# sch_camera.net
KiCad netlist of a schematic drawn in Altium Designer
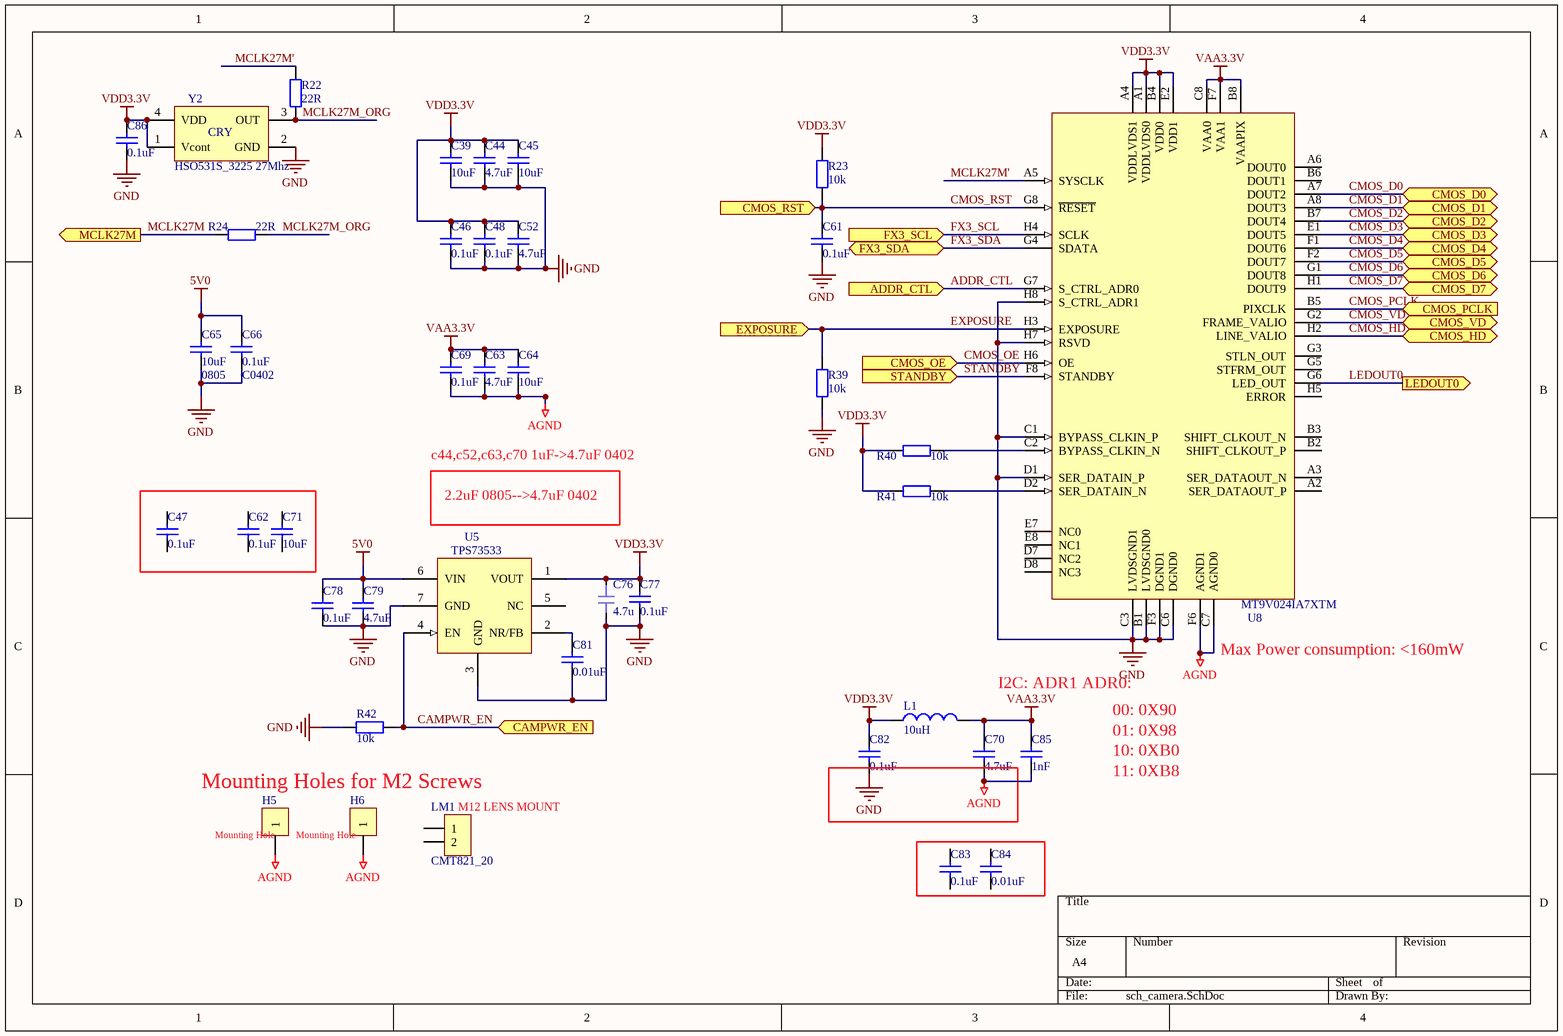
[diagram p0: sch_camera.SchDoc]

(export (version "E")
  (design (tool "Eeschema 10.0.6"))
  (components
    (comp (ref "C39")
      (value "10uF")
      (footprint "0805C")
      (description "Capacitor")
      (fields (field (name "PUBLISHER") "Altium Limited"))
      (libsource (lib "Miscellaneous Devices") (part "Cap"))
    )
    (comp (ref "C44")
      (value "4.7uF")
      (footprint "0402C")
      (description "Capacitor")
      (fields (field (name "PUBLISHER") "Altium Limited"))
      (libsource (lib "Miscellaneous Devices") (part "Cap"))
    )
    (comp (ref "C45")
      (value "10uF")
      (footprint "0805C")
      (description "Capacitor")
      (fields (field (name "PUBLISHER") "Altium Limited"))
      (libsource (lib "Miscellaneous Devices") (part "Cap"))
    )
    (comp (ref "C46")
      (value "0.1uF")
      (footprint "0402C")
      (description "Capacitor")
      (fields (field (name "PUBLISHER") "Altium Limited"))
      (libsource (lib "Miscellaneous Devices") (part "Cap"))
    )
    (comp (ref "C47")
      (value "0.1uF")
      (footprint "0402C")
      (description "Capacitor")
      (fields (field (name "PUBLISHER") "Altium Limited"))
      (libsource (lib "Miscellaneous Devices") (part "Cap"))
    )
    (comp (ref "C48")
      (value "0.1uF")
      (footprint "0402C")
      (description "Capacitor")
      (fields (field (name "PUBLISHER") "Altium Limited"))
      (libsource (lib "Miscellaneous Devices") (part "Cap"))
    )
    (comp (ref "C52")
      (value "4.7uF")
      (footprint "0402C")
      (description "Capacitor")
      (fields (field (name "PUBLISHER") "Altium Limited"))
      (libsource (lib "Miscellaneous Devices") (part "Cap"))
    )
    (comp (ref "C61")
      (value "0.1uF")
      (footprint "0402C_L")
      (description "Capacitor")
      (fields (field (name "PUBLISHER") "Altium Limited"))
      (libsource (lib "Miscellaneous Devices") (part "Cap"))
    )
    (comp (ref "C62")
      (value "0.1uF")
      (footprint "0402C")
      (description "Capacitor")
      (fields (field (name "PUBLISHER") "Altium Limited"))
      (libsource (lib "Miscellaneous Devices") (part "Cap"))
    )
    (comp (ref "C63")
      (value "4.7uF")
      (footprint "0402C")
      (description "Capacitor")
      (fields (field (name "PUBLISHER") "Altium Limited"))
      (libsource (lib "Miscellaneous Devices") (part "Cap"))
    )
    (comp (ref "C64")
      (value "10uF")
      (footprint "0805C")
      (description "Capacitor")
      (fields (field (name "PUBLISHER") "Altium Limited"))
      (libsource (lib "Miscellaneous Devices") (part "Cap"))
    )
    (comp (ref "C65")
      (value "10uF")
      (footprint "0805C")
      (description "Capacitor")
      (fields (field (name "ALTIUM_VALUE") "0805") (field (name "PUBLISHER") "Altium Limited"))
      (libsource (lib "Miscellaneous Devices") (part "Cap"))
    )
    (comp (ref "C66")
      (value "0.1uF")
      (footprint "0402C")
      (description "Capacitor")
      (fields (field (name "ALTIUM_VALUE") "C0402") (field (name "PUBLISHER") "Altium Limited"))
      (libsource (lib "Miscellaneous Devices") (part "Cap"))
    )
    (comp (ref "C69")
      (value "0.1uF")
      (footprint "0402C")
      (description "Capacitor")
      (fields (field (name "PUBLISHER") "Altium Limited"))
      (libsource (lib "Miscellaneous Devices") (part "Cap"))
    )
    (comp (ref "C70")
      (value "4.7uF")
      (footprint "0402C")
      (description "Capacitor")
      (fields (field (name "PUBLISHER") "Altium Limited"))
      (libsource (lib "Miscellaneous Devices") (part "Cap"))
    )
    (comp (ref "C71")
      (value "10uF")
      (footprint "0805C")
      (description "Capacitor")
      (fields (field (name "PUBLISHER") "Altium Limited"))
      (libsource (lib "Miscellaneous Devices") (part "Cap"))
    )
    (comp (ref "C76")
      (value "4.7u")
      (footprint "0402C_L")
      (description "CC0402MRX5R5BB475")
      (libsource (lib "V0P1") (part "cap0402"))
    )
    (comp (ref "C77")
      (value "0.1uF")
      (footprint "0402C_L")
      (description "Capacitor")
      (fields (field (name "PUBLISHER") "Altium Limited"))
      (libsource (lib "Miscellaneous Devices") (part "Cap"))
    )
    (comp (ref "C78")
      (value "0.1uF")
      (footprint "0402C")
      (description "Capacitor")
      (fields (field (name "PUBLISHER") "Altium Limited"))
      (libsource (lib "Miscellaneous Devices") (part "Cap"))
    )
    (comp (ref "C79")
      (value "4.7uF")
      (footprint "0402C_L")
      (description "Capacitor")
      (fields (field (name "Comment") "1uF") (field (name "PUBLISHER") "Altium Limited"))
      (libsource (lib "Miscellaneous Devices") (part "Cap"))
    )
    (comp (ref "C81")
      (value "0.01uF")
      (footprint "0402C_L")
      (description "Capacitor")
      (fields (field (name "PUBLISHER") "Altium Limited"))
      (libsource (lib "Miscellaneous Devices") (part "Cap"))
    )
    (comp (ref "C82")
      (value "0.1uF")
      (footprint "0402C_L")
      (description "Capacitor")
      (fields (field (name "PUBLISHER") "Altium Limited"))
      (libsource (lib "Miscellaneous Devices") (part "Cap"))
    )
    (comp (ref "C83")
      (value "0.1uF")
      (footprint "0402C_L")
      (description "Capacitor")
      (fields (field (name "PUBLISHER") "Altium Limited"))
      (libsource (lib "Miscellaneous Devices") (part "Cap"))
    )
    (comp (ref "C84")
      (value "0.01uF")
      (footprint "0402C_L")
      (description "Capacitor")
      (fields (field (name "PUBLISHER") "Altium Limited"))
      (libsource (lib "Miscellaneous Devices") (part "Cap"))
    )
    (comp (ref "C85")
      (value "1nF")
      (footprint "0402C_L")
      (description "Capacitor")
      (fields (field (name "PUBLISHER") "Altium Limited"))
      (libsource (lib "Miscellaneous Devices") (part "Cap"))
    )
    (comp (ref "C86")
      (value "0.1uF")
      (footprint "0402C_L")
      (description "Capacitor")
      (fields (field (name "PUBLISHER") "Altium Limited"))
      (libsource (lib "Miscellaneous Devices") (part "Cap"))
    )
    (comp (ref "H5")
      (value "CON1")
      (footprint "PAD_M3_D350_450")
      (description "Connector")
      (libsource (lib "SuperSchLib") (part "CON1"))
    )
    (comp (ref "H6")
      (value "CON1")
      (footprint "PAD_M3_D350_450")
      (description "Connector")
      (libsource (lib "SuperSchLib") (part "CON1"))
    )
    (comp (ref "L1")
      (value "10uH")
      (footprint "0805R")
      (description "Inductor")
      (libsource (lib "SWUST_ROBOT") (part "Inductor"))
    )
    (comp (ref "LM1")
      (value "CMT821_20")
      (footprint "PAD_M3_D350_450")
      (description "Connector")
      (libsource (lib "SuperSchLib") (part "CON2"))
    )
    (comp (ref "R22")
      (value "22R")
      (footprint "0402R_L")
      (description "Resistor")
      (fields (field (name "Comment") "0R") (field (name "PUBLISHER") "Altium Limited"))
      (libsource (lib "SZG") (part "Resistor"))
    )
    (comp (ref "R23")
      (value "10k")
      (footprint "0402R_L")
      (description "Resistor")
      (fields (field (name "Comment") "10K") (field (name "PUBLISHER") "Altium Limited"))
      (libsource (lib "") (part "Resistor_2"))
    )
    (comp (ref "R24")
      (value "22R")
      (footprint "0402R")
      (description "Resistor")
      (fields (field (name "PUBLISHER") "Altium Limited"))
      (libsource (lib "") (part "Resistor_1"))
    )
    (comp (ref "R39")
      (value "10k")
      (footprint "0402R_L")
      (description "Resistor")
      (fields (field (name "Comment") "10K") (field (name "PUBLISHER") "Altium Limited"))
      (libsource (lib "SZG") (part "Resistor"))
    )
    (comp (ref "R40")
      (value "10k")
      (footprint "0402R_L")
      (description "Resistor")
      (fields (field (name "Comment") "10K") (field (name "PUBLISHER") "Altium Limited"))
      (libsource (lib "") (part "Resistor_3"))
    )
    (comp (ref "R41")
      (value "10k")
      (footprint "0402R_L")
      (description "Resistor")
      (fields (field (name "Comment") "10K") (field (name "PUBLISHER") "Altium Limited"))
      (libsource (lib "") (part "Resistor_3"))
    )
    (comp (ref "R42")
      (value "10k")
      (footprint "0402R_L")
      (description "Resistor")
      (fields (field (name "Comment") "10K") (field (name "PUBLISHER") "Altium Limited"))
      (libsource (lib "") (part "Resistor_3"))
    )
    (comp (ref "U5")
      (value "TPS73533")
      (footprint "SON6_P65L21W21H8_DRV")
      (libsource (lib "SZG") (part "TPS73533"))
    )
    (comp (ref "U8")
      (value "MT9V024IA7XTM")
      (footprint "IBGA52_8X8_P100L90W90H90R")
      (libsource (lib "SZG") (part "MT9V024IA7XTM"))
    )
    (comp (ref "Y2")
      (value "HSO531S_3225 27Mhz")
      (footprint "XTAL_3225")
      (description "有源晶振")
      (libsource (lib "超集元件库") (part "CRY"))
    )
  )
  (nets
    (net (code "1") (name "/ADDR_CTL") (class "Default")
      (node (ref "U8") (pin "G7") (pinfunction "S_CTRL_ADR0_G7") (pintype "input"))
    )
    (net (code "2") (name "/CAMPWR_EN") (class "Default")
      (node (ref "R42") (pin "1") (pinfunction "1_1") (pintype "passive"))
      (node (ref "U5") (pin "4") (pinfunction "EN_4") (pintype "input"))
    )
    (net (code "3") (name "/CMOS_D0") (class "Default")
      (node (ref "U8") (pin "A7") (pinfunction "DOUT2_A7") (pintype "passive"))
    )
    (net (code "4") (name "/CMOS_D1") (class "Default")
      (node (ref "U8") (pin "A8") (pinfunction "DOUT3_A8") (pintype "passive"))
    )
    (net (code "5") (name "/CMOS_D2") (class "Default")
      (node (ref "U8") (pin "B7") (pinfunction "DOUT4_B7") (pintype "passive"))
    )
    (net (code "6") (name "/CMOS_D3") (class "Default")
      (node (ref "U8") (pin "E1") (pinfunction "DOUT5_E1") (pintype "passive"))
    )
    (net (code "7") (name "/CMOS_D4") (class "Default")
      (node (ref "U8") (pin "F1") (pinfunction "DOUT6_F1") (pintype "passive"))
    )
    (net (code "8") (name "/CMOS_D5") (class "Default")
      (node (ref "U8") (pin "F2") (pinfunction "DOUT7_F2") (pintype "passive"))
    )
    (net (code "9") (name "/CMOS_D6") (class "Default")
      (node (ref "U8") (pin "G1") (pinfunction "DOUT8_G1") (pintype "passive"))
    )
    (net (code "10") (name "/CMOS_D7") (class "Default")
      (node (ref "U8") (pin "H1") (pinfunction "DOUT9_H1") (pintype "passive"))
    )
    (net (code "11") (name "/CMOS_HD") (class "Default")
      (node (ref "U8") (pin "H2") (pinfunction "LINE_VALIO_H2") (pintype "passive"))
    )
    (net (code "12") (name "/CMOS_OE") (class "Default")
      (node (ref "U8") (pin "H6") (pinfunction "OE_H6") (pintype "input"))
    )
    (net (code "13") (name "/CMOS_PCLK") (class "Default")
      (node (ref "U8") (pin "B5") (pinfunction "PIXCLK_B5") (pintype "passive"))
    )
    (net (code "14") (name "/CMOS_RST") (class "Default")
      (node (ref "C61") (pin "2") (pinfunction "2_2") (pintype "passive"))
      (node (ref "R23") (pin "1") (pinfunction "1_1") (pintype "passive"))
      (node (ref "U8") (pin "G8") (pinfunction "~{RESET}_G8") (pintype "input"))
    )
    (net (code "15") (name "/CMOS_VD") (class "Default")
      (node (ref "U8") (pin "G2") (pinfunction "FRAME_VALIO_G2") (pintype "passive"))
    )
    (net (code "16") (name "/EXPOSURE") (class "Default")
      (node (ref "R39") (pin "1") (pinfunction "1_1") (pintype "passive"))
      (node (ref "U8") (pin "H3") (pinfunction "EXPOSURE_H3") (pintype "input"))
    )
    (net (code "17") (name "/FX3_SCL") (class "Default")
      (node (ref "U8") (pin "H4") (pinfunction "SCLK_H4") (pintype "input"))
    )
    (net (code "18") (name "/FX3_SDA") (class "Default")
      (node (ref "U8") (pin "G4") (pinfunction "SDATA_G4") (pintype "passive"))
    )
    (net (code "19") (name "/LEDOUT0") (class "Default")
      (node (ref "U8") (pin "G6") (pinfunction "LED_OUT_G6") (pintype "passive"))
    )
    (net (code "20") (name "/MCLK27M") (class "Default")
      (node (ref "R24") (pin "1") (pinfunction "1_1") (pintype "passive"))
    )
    (net (code "21") (name "/MCLK27M'") (class "Default")
      (node (ref "R22") (pin "1") (pinfunction "1_1") (pintype "passive"))
      (node (ref "U8") (pin "A5") (pinfunction "SYSCLK_A5") (pintype "input"))
    )
    (net (code "22") (name "/MCLK27M_ORG") (class "Default")
      (node (ref "R22") (pin "2") (pinfunction "2_2") (pintype "passive"))
      (node (ref "R24") (pin "2") (pinfunction "2_2") (pintype "passive"))
      (node (ref "Y2") (pin "3") (pinfunction "OUT_3") (pintype "passive"))
    )
    (net (code "23") (name "/STANDBY") (class "Default")
      (node (ref "U8") (pin "F8") (pinfunction "STANDBY_F8") (pintype "input"))
    )
    (net (code "24") (name "5V0") (class "Default")
      (node (ref "C65") (pin "2") (pinfunction "2_2") (pintype "passive"))
      (node (ref "C66") (pin "2") (pinfunction "2_2") (pintype "passive"))
      (node (ref "C78") (pin "2") (pinfunction "2_2") (pintype "passive"))
      (node (ref "C79") (pin "2") (pinfunction "2_2") (pintype "passive"))
      (node (ref "U5") (pin "6") (pinfunction "VIN_6") (pintype "passive"))
    )
    (net (code "25") (name "AGND") (class "Default")
      (node (ref "C63") (pin "1") (pinfunction "1_1") (pintype "passive"))
      (node (ref "C64") (pin "1") (pinfunction "1_1") (pintype "passive"))
      (node (ref "C69") (pin "1") (pinfunction "1_1") (pintype "passive"))
      (node (ref "C70") (pin "1") (pinfunction "1_1") (pintype "passive"))
      (node (ref "C85") (pin "1") (pinfunction "1_1") (pintype "passive"))
      (node (ref "H5") (pin "1") (pinfunction "1_1") (pintype "passive"))
      (node (ref "H6") (pin "1") (pinfunction "1_1") (pintype "passive"))
      (node (ref "U8") (pin "C7") (pinfunction "AGND0_C7") (pintype "power_in"))
      (node (ref "U8") (pin "F6") (pinfunction "AGND1_F6") (pintype "power_in"))
    )
    (net (code "26") (name "GND") (class "Default")
      (node (ref "C39") (pin "1") (pinfunction "1_1") (pintype "passive"))
      (node (ref "C44") (pin "1") (pinfunction "1_1") (pintype "passive"))
      (node (ref "C45") (pin "1") (pinfunction "1_1") (pintype "passive"))
      (node (ref "C46") (pin "1") (pinfunction "1_1") (pintype "passive"))
      (node (ref "C48") (pin "1") (pinfunction "1_1") (pintype "passive"))
      (node (ref "C52") (pin "1") (pinfunction "1_1") (pintype "passive"))
      (node (ref "C61") (pin "1") (pinfunction "1_1") (pintype "passive"))
      (node (ref "C65") (pin "1") (pinfunction "1_1") (pintype "passive"))
      (node (ref "C66") (pin "1") (pinfunction "1_1") (pintype "passive"))
      (node (ref "C76") (pin "2") (pinfunction "2_2") (pintype "passive"))
      (node (ref "C77") (pin "1") (pinfunction "1_1") (pintype "passive"))
      (node (ref "C78") (pin "1") (pinfunction "1_1") (pintype "passive"))
      (node (ref "C79") (pin "1") (pinfunction "1_1") (pintype "passive"))
      (node (ref "C81") (pin "1") (pinfunction "1_1") (pintype "passive"))
      (node (ref "C82") (pin "1") (pinfunction "1_1") (pintype "passive"))
      (node (ref "C86") (pin "1") (pinfunction "1_1") (pintype "passive"))
      (node (ref "R39") (pin "2") (pinfunction "2_2") (pintype "passive"))
      (node (ref "R42") (pin "2") (pinfunction "2_2") (pintype "passive"))
      (node (ref "U5") (pin "3") (pinfunction "GND_3") (pintype "passive"))
      (node (ref "U5") (pin "7") (pinfunction "GND_7") (pintype "passive"))
      (node (ref "U8") (pin "B1") (pinfunction "LVDSGND0_B1") (pintype "power_in"))
      (node (ref "U8") (pin "C1") (pinfunction "BYPASS_CLKIN_P_C1") (pintype "input"))
      (node (ref "U8") (pin "C3") (pinfunction "LVDSGND1_C3") (pintype "power_in"))
      (node (ref "U8") (pin "C6") (pinfunction "DGND0_C6") (pintype "power_in"))
      (node (ref "U8") (pin "D1") (pinfunction "SER_DATAIN_P_D1") (pintype "input"))
      (node (ref "U8") (pin "F3") (pinfunction "DGND1_F3") (pintype "power_in"))
      (node (ref "U8") (pin "H7") (pinfunction "RSVD_H7") (pintype "input"))
      (node (ref "U8") (pin "H8") (pinfunction "S_CTRL_ADR1_H8") (pintype "input"))
      (node (ref "Y2") (pin "2") (pinfunction "GND_2") (pintype "passive"))
    )
    (net (code "27") (name "Net-(U5-NR{slash}FB)") (class "Default")
      (node (ref "C81") (pin "2") (pinfunction "2_2") (pintype "passive"))
      (node (ref "U5") (pin "2") (pinfunction "NR/FB_2") (pintype "passive"))
    )
    (net (code "28") (name "Net-(U8-BYPASS_CLKIN_N)") (class "Default")
      (node (ref "R40") (pin "1") (pinfunction "1_1") (pintype "passive"))
      (node (ref "U8") (pin "C2") (pinfunction "BYPASS_CLKIN_N_C2") (pintype "input"))
    )
    (net (code "29") (name "Net-(U8-SER_DATAIN_N)") (class "Default")
      (node (ref "R41") (pin "1") (pinfunction "1_1") (pintype "passive"))
      (node (ref "U8") (pin "D2") (pinfunction "SER_DATAIN_N_D2") (pintype "input"))
    )
    (net (code "30") (name "VAA3.3V") (class "Default")
      (node (ref "C63") (pin "2") (pinfunction "2_2") (pintype "passive"))
      (node (ref "C64") (pin "2") (pinfunction "2_2") (pintype "passive"))
      (node (ref "C69") (pin "2") (pinfunction "2_2") (pintype "passive"))
      (node (ref "C70") (pin "2") (pinfunction "2_2") (pintype "passive"))
      (node (ref "C85") (pin "2") (pinfunction "2_2") (pintype "passive"))
      (node (ref "L1") (pin "2") (pinfunction "2_2") (pintype "passive"))
      (node (ref "U8") (pin "B8") (pinfunction "VAAPIX_B8") (pintype "power_in"))
      (node (ref "U8") (pin "C8") (pinfunction "VAA0_C8") (pintype "power_in"))
      (node (ref "U8") (pin "F7") (pinfunction "VAA1_F7") (pintype "power_in"))
    )
    (net (code "31") (name "VDD3.3V") (class "Default")
      (node (ref "C39") (pin "2") (pinfunction "2_2") (pintype "passive"))
      (node (ref "C44") (pin "2") (pinfunction "2_2") (pintype "passive"))
      (node (ref "C45") (pin "2") (pinfunction "2_2") (pintype "passive"))
      (node (ref "C46") (pin "2") (pinfunction "2_2") (pintype "passive"))
      (node (ref "C48") (pin "2") (pinfunction "2_2") (pintype "passive"))
      (node (ref "C52") (pin "2") (pinfunction "2_2") (pintype "passive"))
      (node (ref "C76") (pin "1") (pinfunction "1_1") (pintype "passive"))
      (node (ref "C77") (pin "2") (pinfunction "2_2") (pintype "passive"))
      (node (ref "C82") (pin "2") (pinfunction "2_2") (pintype "passive"))
      (node (ref "C86") (pin "2") (pinfunction "2_2") (pintype "passive"))
      (node (ref "L1") (pin "1") (pinfunction "1_1") (pintype "passive"))
      (node (ref "R23") (pin "2") (pinfunction "2_2") (pintype "passive"))
      (node (ref "R40") (pin "2") (pinfunction "2_2") (pintype "passive"))
      (node (ref "R41") (pin "2") (pinfunction "2_2") (pintype "passive"))
      (node (ref "U5") (pin "1") (pinfunction "VOUT_1") (pintype "passive"))
      (node (ref "U8") (pin "A1") (pinfunction "VDDLVDS0_A1") (pintype "power_in"))
      (node (ref "U8") (pin "A4") (pinfunction "VDDLVDS1_A4") (pintype "power_in"))
      (node (ref "U8") (pin "B4") (pinfunction "VDD0_B4") (pintype "power_in"))
      (node (ref "U8") (pin "E2") (pinfunction "VDD1_E2") (pintype "power_in"))
      (node (ref "Y2") (pin "1") (pinfunction "Vcont_1") (pintype "passive"))
      (node (ref "Y2") (pin "4") (pinfunction "VDD_4") (pintype "passive"))
    )
    (net (code "32") (name "unconnected-(C47-Pad1)") (class "Default")
      (node (ref "C47") (pin "1") (pinfunction "1_1") (pintype "passive"))
    )
    (net (code "33") (name "unconnected-(C47-Pad2)") (class "Default")
      (node (ref "C47") (pin "2") (pinfunction "2_2") (pintype "passive"))
    )
    (net (code "34") (name "unconnected-(C62-Pad1)") (class "Default")
      (node (ref "C62") (pin "1") (pinfunction "1_1") (pintype "passive"))
    )
    (net (code "35") (name "unconnected-(C62-Pad2)") (class "Default")
      (node (ref "C62") (pin "2") (pinfunction "2_2") (pintype "passive"))
    )
    (net (code "36") (name "unconnected-(C71-Pad1)") (class "Default")
      (node (ref "C71") (pin "1") (pinfunction "1_1") (pintype "passive"))
    )
    (net (code "37") (name "unconnected-(C71-Pad2)") (class "Default")
      (node (ref "C71") (pin "2") (pinfunction "2_2") (pintype "passive"))
    )
    (net (code "38") (name "unconnected-(C83-Pad1)") (class "Default")
      (node (ref "C83") (pin "1") (pinfunction "1_1") (pintype "passive"))
    )
    (net (code "39") (name "unconnected-(C83-Pad2)") (class "Default")
      (node (ref "C83") (pin "2") (pinfunction "2_2") (pintype "passive"))
    )
    (net (code "40") (name "unconnected-(C84-Pad1)") (class "Default")
      (node (ref "C84") (pin "1") (pinfunction "1_1") (pintype "passive"))
    )
    (net (code "41") (name "unconnected-(C84-Pad2)") (class "Default")
      (node (ref "C84") (pin "2") (pinfunction "2_2") (pintype "passive"))
    )
    (net (code "42") (name "unconnected-(LM1-Pad1)") (class "Default")
      (node (ref "LM1") (pin "1") (pinfunction "1_1") (pintype "passive"))
    )
    (net (code "43") (name "unconnected-(LM1-Pad2)") (class "Default")
      (node (ref "LM1") (pin "2") (pinfunction "2_2") (pintype "passive"))
    )
    (net (code "44") (name "unconnected-(U5-NC-Pad5)") (class "Default")
      (node (ref "U5") (pin "5") (pinfunction "NC_5") (pintype "passive"))
    )
    (net (code "45") (name "unconnected-(U8-DOUT0-PadA6)") (class "Default")
      (node (ref "U8") (pin "A6") (pinfunction "DOUT0_A6") (pintype "passive"))
    )
    (net (code "46") (name "unconnected-(U8-DOUT1-PadB6)") (class "Default")
      (node (ref "U8") (pin "B6") (pinfunction "DOUT1_B6") (pintype "passive"))
    )
    (net (code "47") (name "unconnected-(U8-ERROR-PadH5)") (class "Default")
      (node (ref "U8") (pin "H5") (pinfunction "ERROR_H5") (pintype "passive"))
    )
    (net (code "48") (name "unconnected-(U8-NC0-PadE7)") (class "Default")
      (node (ref "U8") (pin "E7") (pinfunction "NC0_E7") (pintype "passive"))
    )
    (net (code "49") (name "unconnected-(U8-NC1-PadE8)") (class "Default")
      (node (ref "U8") (pin "E8") (pinfunction "NC1_E8") (pintype "power_in"))
    )
    (net (code "50") (name "unconnected-(U8-NC2-PadD7)") (class "Default")
      (node (ref "U8") (pin "D7") (pinfunction "NC2_D7") (pintype "power_in"))
    )
    (net (code "51") (name "unconnected-(U8-NC3-PadD8)") (class "Default")
      (node (ref "U8") (pin "D8") (pinfunction "NC3_D8") (pintype "power_in"))
    )
    (net (code "52") (name "unconnected-(U8-SER_DATAOUT_N-PadA3)") (class "Default")
      (node (ref "U8") (pin "A3") (pinfunction "SER_DATAOUT_N_A3") (pintype "passive"))
    )
    (net (code "53") (name "unconnected-(U8-SER_DATAOUT_P-PadA2)") (class "Default")
      (node (ref "U8") (pin "A2") (pinfunction "SER_DATAOUT_P_A2") (pintype "passive"))
    )
    (net (code "54") (name "unconnected-(U8-SHIFT_CLKOUT_N-PadB3)") (class "Default")
      (node (ref "U8") (pin "B3") (pinfunction "SHIFT_CLKOUT_N_B3") (pintype "passive"))
    )
    (net (code "55") (name "unconnected-(U8-SHIFT_CLKOUT_P-PadB2)") (class "Default")
      (node (ref "U8") (pin "B2") (pinfunction "SHIFT_CLKOUT_P_B2") (pintype "passive"))
    )
    (net (code "56") (name "unconnected-(U8-STFRM_OUT-PadG5)") (class "Default")
      (node (ref "U8") (pin "G5") (pinfunction "STFRM_OUT_G5") (pintype "passive"))
    )
    (net (code "57") (name "unconnected-(U8-STLN_OUT-PadG3)") (class "Default")
      (node (ref "U8") (pin "G3") (pinfunction "STLN_OUT_G3") (pintype "passive"))
    )
  )
)
